# bleumaus-oshchip-mk-1_0_1.net
KiCad netlist of a schematic drawn in EAGLE
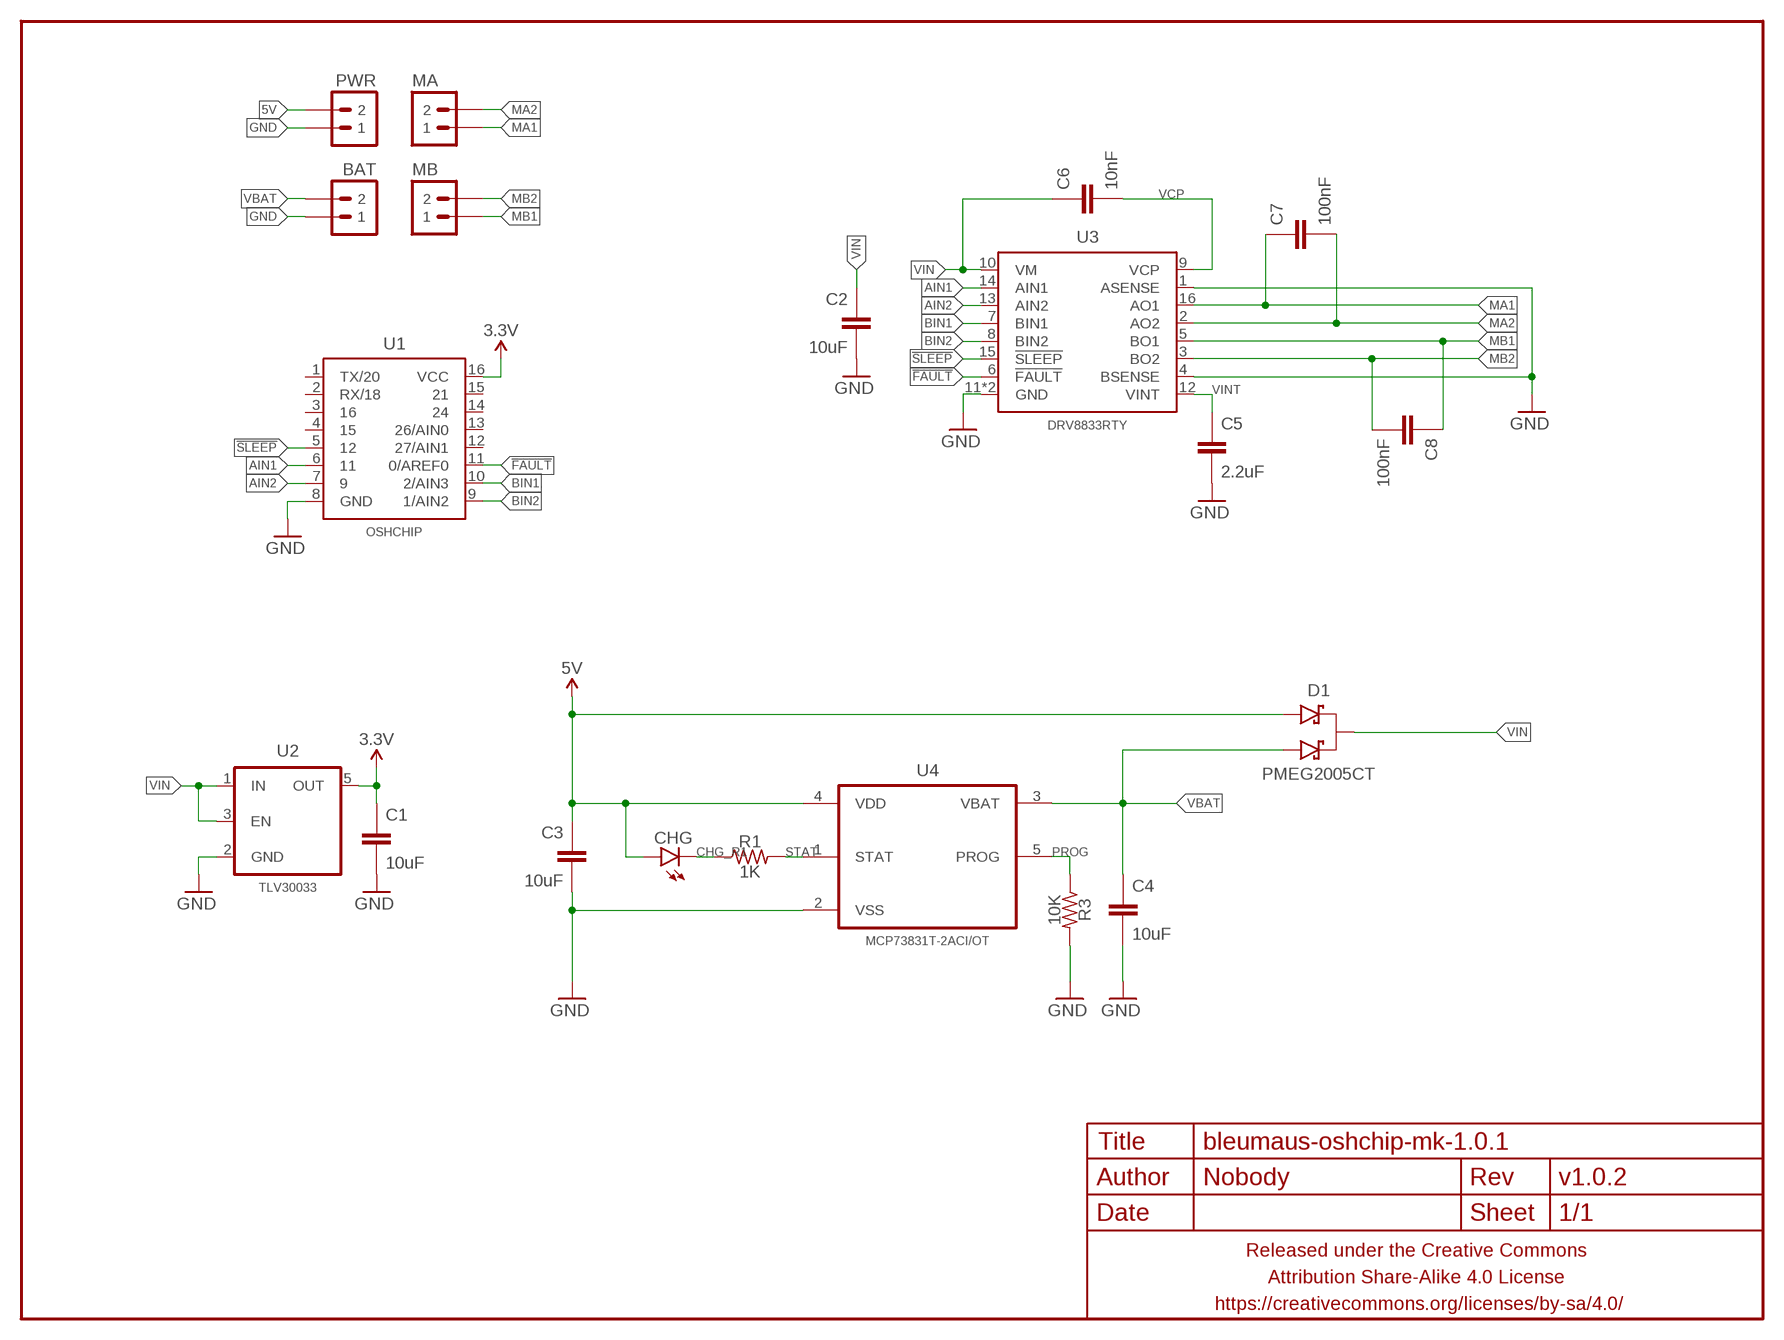
[diagram p0: schematic, sheet 1]

(export (version "E")
  (design (tool "Eeschema 10.0.6"))
  (components
    (comp (ref "BAT")
      (value "M02PTH-2MM")
      (footprint "eagle-import:1X02-2MM-PTH")
      (libsource (lib "eagle-import") (part "M02PTH-2MM"))
    )
    (comp (ref "C1")
      (value "10uF")
      (footprint "eagle-import:C0402")
      (libsource (lib "eagle-import") (part "CAPACITOR-CERAMICC0402"))
    )
    (comp (ref "C2")
      (value "10uF")
      (footprint "eagle-import:C1206")
      (libsource (lib "eagle-import") (part "CAPACITOR-CERAMICC1206"))
    )
    (comp (ref "C3")
      (value "10uF")
      (footprint "eagle-import:C0402")
      (libsource (lib "eagle-import") (part "CAPACITOR-CERAMICC0402"))
    )
    (comp (ref "C4")
      (value "10uF")
      (footprint "eagle-import:C0402")
      (libsource (lib "eagle-import") (part "CAPACITOR-CERAMICC0402"))
    )
    (comp (ref "C5")
      (value "2.2uF")
      (footprint "eagle-import:C0402")
      (libsource (lib "eagle-import") (part "CAPACITOR-CERAMICC0402"))
    )
    (comp (ref "C6")
      (value "10nF")
      (footprint "eagle-import:C0402")
      (libsource (lib "eagle-import") (part "CAPACITOR-CERAMICC0402"))
    )
    (comp (ref "C7")
      (value "100nF")
      (footprint "eagle-import:C0402")
      (libsource (lib "eagle-import") (part "CAPACITOR-CERAMICC0402"))
    )
    (comp (ref "C8")
      (value "100nF")
      (footprint "eagle-import:C0402")
      (libsource (lib "eagle-import") (part "CAPACITOR-CERAMICC0402"))
    )
    (comp (ref "CHG")
      (value "LED0603-TIGHT")
      (footprint "eagle-import:LED-0603-TIGHT")
      (libsource (lib "eagle-import") (part "LED0603-TIGHT"))
    )
    (comp (ref "D1")
      (value "PMEG2005CT")
      (footprint "eagle-import:SOT23")
      (libsource (lib "eagle-import") (part "DIODE-SCHOTTKY-DUALPMEG2005CT"))
    )
    (comp (ref "FRAME1")
      (value "FRAME-LETTERNO_PACKAGE")
      (footprint "eagle-import:DUMMY")
      (fields
        (field (name "DESIGNER") "Nobody")
        (field (name "VERSION") "v01")
        (field (name "VERSION_1") "v1.0.2")
      )
      (libsource (lib "eagle-import") (part "FRAME-LETTERNO_PACKAGE"))
    )
    (comp (ref "MA")
      (value "M02PTH-2MM")
      (footprint "eagle-import:1X02-2MM-PTH")
      (libsource (lib "eagle-import") (part "M02PTH-2MM"))
    )
    (comp (ref "MB")
      (value "M02PTH-2MM")
      (footprint "eagle-import:1X02-2MM-PTH")
      (libsource (lib "eagle-import") (part "M02PTH-2MM"))
    )
    (comp (ref "PWR")
      (value "M02PTH-2MM")
      (footprint "eagle-import:1X02-2MM-PTH")
      (libsource (lib "eagle-import") (part "M02PTH-2MM"))
    )
    (comp (ref "R1")
      (value "1K")
      (footprint "eagle-import:R0402")
      (libsource (lib "eagle-import") (part "RESISTORR0402"))
    )
    (comp (ref "R3")
      (value "10K")
      (footprint "eagle-import:R0402")
      (libsource (lib "eagle-import") (part "RESISTORR0402"))
    )
    (comp (ref "U1")
      (value "OSHCHIP")
      (footprint "eagle-import:DIL16")
      (libsource (lib "eagle-import") (part "OSHCHIP"))
    )
    (comp (ref "U2")
      (value "TLV30033")
      (footprint "eagle-import:SC70-TIGHTER")
      (libsource (lib "eagle-import") (part "V_REG_ENTLV700XXDCK-TIGHTER"))
    )
    (comp (ref "U3")
      (value "DRV8833RTY")
      (footprint "eagle-import:PWQFN-16")
      (libsource (lib "eagle-import") (part "DRV8833RTY"))
    )
    (comp (ref "U4")
      (value "MCP73831T-2ACI/OT")
      (footprint "eagle-import:SOT95P280X145-5N")
      (libsource (lib "eagle-import") (part "MCP73831T-2ACI/OT"))
    )
  )
  (nets
    (net (code "1") (name "/CHG_R1") (class "Default")
      (node (ref "CHG") (pin "C") (pinfunction "C_C") (pintype "passive"))
      (node (ref "R1") (pin "1") (pinfunction "1_1") (pintype "passive"))
    )
    (net (code "2") (name "/PROG") (class "Default")
      (node (ref "R3") (pin "1") (pinfunction "1_1") (pintype "passive"))
      (node (ref "U4") (pin "5") (pinfunction "PROG_5") (pintype "input"))
    )
    (net (code "3") (name "/STAT") (class "Default")
      (node (ref "R1") (pin "2") (pinfunction "2_2") (pintype "passive"))
      (node (ref "U4") (pin "1") (pinfunction "STAT_1") (pintype "output"))
    )
    (net (code "4") (name "/VCP") (class "Default")
      (node (ref "C6") (pin "2") (pinfunction "2_2") (pintype "passive"))
      (node (ref "U3") (pin "9") (pinfunction "VCP_9") (pintype "bidirectional"))
    )
    (net (code "5") (name "/VINT") (class "Default")
      (node (ref "C5") (pin "1") (pinfunction "1_1") (pintype "passive"))
      (node (ref "U3") (pin "12") (pinfunction "VINT_12") (pintype "bidirectional"))
    )
    (net (code "6") (name "/~{FAULT}") (class "Default")
      (node (ref "U1") (pin "11") (pinfunction "0/AREF0_11") (pintype "bidirectional"))
      (node (ref "U3") (pin "6") (pinfunction "~{FAULT}_6") (pintype "output"))
    )
    (net (code "7") (name "/~{SLEEP}") (class "Default")
      (node (ref "U1") (pin "5") (pinfunction "12_5") (pintype "bidirectional"))
      (node (ref "U3") (pin "15") (pinfunction "~{SLEEP}_15") (pintype "input"))
    )
    (net (code "8") (name "3.3V") (class "Default")
      (node (ref "C1") (pin "1") (pinfunction "1_1") (pintype "passive"))
      (node (ref "U1") (pin "16") (pinfunction "VCC_16") (pintype "bidirectional"))
      (node (ref "U2") (pin "5") (pinfunction "OUT_5") (pintype "passive"))
    )
    (net (code "9") (name "5V") (class "Default")
      (node (ref "C3") (pin "1") (pinfunction "1_1") (pintype "passive"))
      (node (ref "CHG") (pin "A") (pinfunction "A_A") (pintype "passive"))
      (node (ref "D1") (pin "1") (pinfunction "A1_1") (pintype "passive"))
      (node (ref "PWR") (pin "P$2") (pinfunction "2_P$2") (pintype "passive"))
      (node (ref "U4") (pin "4") (pinfunction "VDD_4") (pintype "power_in"))
    )
    (net (code "10") (name "AIN1") (class "Default")
      (node (ref "U1") (pin "6") (pinfunction "11_6") (pintype "bidirectional"))
      (node (ref "U3") (pin "14") (pinfunction "AIN1_14") (pintype "input"))
    )
    (net (code "11") (name "AIN2") (class "Default")
      (node (ref "U1") (pin "7") (pinfunction "9_7") (pintype "bidirectional"))
      (node (ref "U3") (pin "13") (pinfunction "AIN2_13") (pintype "input"))
    )
    (net (code "12") (name "BIN1") (class "Default")
      (node (ref "U1") (pin "10") (pinfunction "2/AIN3_10") (pintype "bidirectional"))
      (node (ref "U3") (pin "7") (pinfunction "BIN1_7") (pintype "input"))
    )
    (net (code "13") (name "BIN2") (class "Default")
      (node (ref "U1") (pin "9") (pinfunction "1/AIN2_9") (pintype "bidirectional"))
      (node (ref "U3") (pin "8") (pinfunction "BIN2_8") (pintype "input"))
    )
    (net (code "14") (name "GND") (class "Default")
      (node (ref "BAT") (pin "P$1") (pinfunction "1_P$1") (pintype "passive"))
      (node (ref "C1") (pin "2") (pinfunction "2_2") (pintype "passive"))
      (node (ref "C2") (pin "2") (pinfunction "2_2") (pintype "passive"))
      (node (ref "C3") (pin "2") (pinfunction "2_2") (pintype "passive"))
      (node (ref "C4") (pin "2") (pinfunction "2_2") (pintype "passive"))
      (node (ref "C5") (pin "2") (pinfunction "2_2") (pintype "passive"))
      (node (ref "PWR") (pin "P$1") (pinfunction "1_P$1") (pintype "passive"))
      (node (ref "R3") (pin "2") (pinfunction "2_2") (pintype "passive"))
      (node (ref "U1") (pin "8") (pinfunction "GND_8") (pintype "bidirectional"))
      (node (ref "U2") (pin "2") (pinfunction "GND_2") (pintype "input"))
      (node (ref "U3") (pin "1") (pinfunction "ASENSE_1") (pintype "bidirectional"))
      (node (ref "U3") (pin "11") (pinfunction "GND_11") (pintype "bidirectional"))
      (node (ref "U3") (pin "17") (pinfunction "GND_17") (pintype "bidirectional"))
      (node (ref "U3") (pin "4") (pinfunction "BSENSE_4") (pintype "bidirectional"))
      (node (ref "U4") (pin "2") (pinfunction "VSS_2") (pintype "power_in"))
    )
    (net (code "15") (name "MA1") (class "Default")
      (node (ref "C7") (pin "1") (pinfunction "1_1") (pintype "passive"))
      (node (ref "MA") (pin "P$1") (pinfunction "1_P$1") (pintype "passive"))
      (node (ref "U3") (pin "16") (pinfunction "AO1_16") (pintype "bidirectional"))
    )
    (net (code "16") (name "MA2") (class "Default")
      (node (ref "C7") (pin "2") (pinfunction "2_2") (pintype "passive"))
      (node (ref "MA") (pin "P$2") (pinfunction "2_P$2") (pintype "passive"))
      (node (ref "U3") (pin "2") (pinfunction "AO2_2") (pintype "bidirectional"))
    )
    (net (code "17") (name "MB1") (class "Default")
      (node (ref "C8") (pin "1") (pinfunction "1_1") (pintype "passive"))
      (node (ref "MB") (pin "P$1") (pinfunction "1_P$1") (pintype "passive"))
      (node (ref "U3") (pin "5") (pinfunction "BO1_5") (pintype "bidirectional"))
    )
    (net (code "18") (name "MB2") (class "Default")
      (node (ref "C8") (pin "2") (pinfunction "2_2") (pintype "passive"))
      (node (ref "MB") (pin "P$2") (pinfunction "2_P$2") (pintype "passive"))
      (node (ref "U3") (pin "3") (pinfunction "BO2_3") (pintype "bidirectional"))
    )
    (net (code "19") (name "VBAT") (class "Default")
      (node (ref "BAT") (pin "P$2") (pinfunction "2_P$2") (pintype "passive"))
      (node (ref "C4") (pin "1") (pinfunction "1_1") (pintype "passive"))
      (node (ref "D1") (pin "2") (pinfunction "A2_2") (pintype "passive"))
      (node (ref "U4") (pin "3") (pinfunction "VBAT_3") (pintype "output"))
    )
    (net (code "20") (name "VIN") (class "Default")
      (node (ref "C2") (pin "1") (pinfunction "1_1") (pintype "passive"))
      (node (ref "C6") (pin "1") (pinfunction "1_1") (pintype "passive"))
      (node (ref "D1") (pin "3") (pinfunction "K_3") (pintype "passive"))
      (node (ref "U2") (pin "1") (pinfunction "IN_1") (pintype "input"))
      (node (ref "U2") (pin "3") (pinfunction "EN_3") (pintype "input"))
      (node (ref "U3") (pin "10") (pinfunction "VM_10") (pintype "bidirectional"))
    )
    (net (code "21") (name "unconnected-(U1-15-Pad4)") (class "Default")
      (node (ref "U1") (pin "4") (pinfunction "15_4") (pintype "bidirectional"))
    )
    (net (code "22") (name "unconnected-(U1-16-Pad3)") (class "Default")
      (node (ref "U1") (pin "3") (pinfunction "16_3") (pintype "bidirectional"))
    )
    (net (code "23") (name "unconnected-(U1-21-Pad15)") (class "Default")
      (node (ref "U1") (pin "15") (pinfunction "21_15") (pintype "bidirectional"))
    )
    (net (code "24") (name "unconnected-(U1-24-Pad14)") (class "Default")
      (node (ref "U1") (pin "14") (pinfunction "24_14") (pintype "bidirectional"))
    )
    (net (code "25") (name "unconnected-(U1-26{slash}AIN0-Pad13)") (class "Default")
      (node (ref "U1") (pin "13") (pinfunction "26/AIN0_13") (pintype "bidirectional"))
    )
    (net (code "26") (name "unconnected-(U1-27{slash}AIN1-Pad12)") (class "Default")
      (node (ref "U1") (pin "12") (pinfunction "27/AIN1_12") (pintype "bidirectional"))
    )
    (net (code "27") (name "unconnected-(U1-RX{slash}18-Pad2)") (class "Default")
      (node (ref "U1") (pin "2") (pinfunction "RX/18_2") (pintype "bidirectional"))
    )
    (net (code "28") (name "unconnected-(U1-TX{slash}20-Pad1)") (class "Default")
      (node (ref "U1") (pin "1") (pinfunction "TX/20_1") (pintype "bidirectional"))
    )
  )
)
